# Schematic_1.net
KiCad netlist of a schematic drawn in Altium Designer
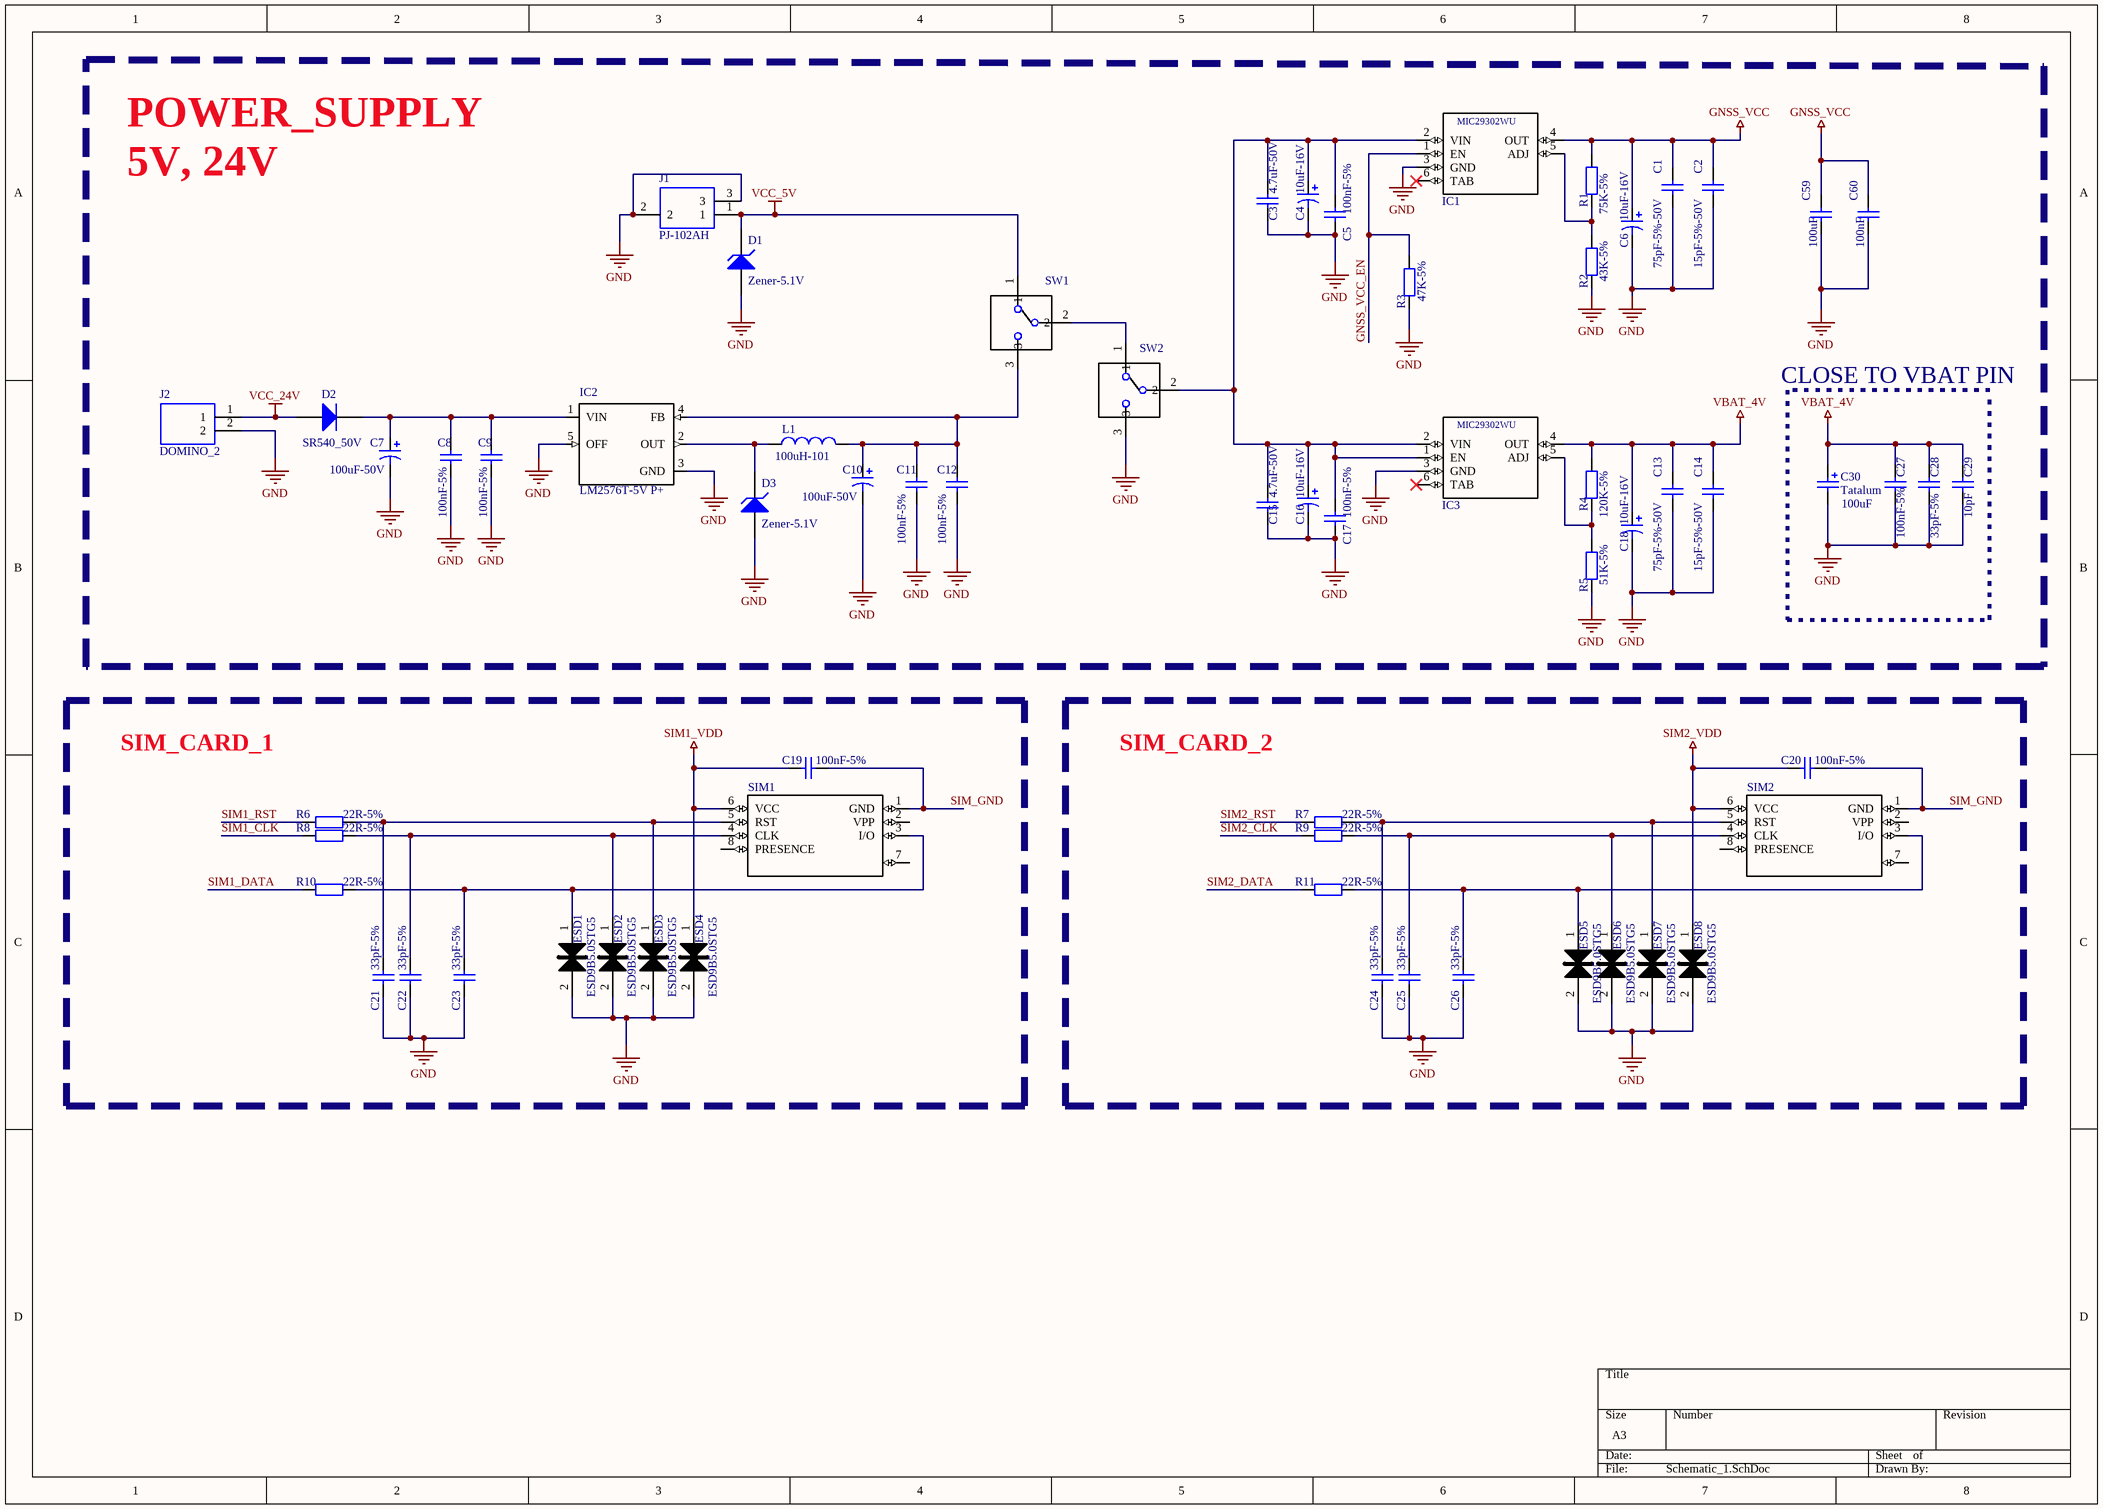
[diagram p0: Schematic_1.SchDoc]

(export (version "E")
  (design (tool "Eeschema 10.0.6"))
  (components
    (comp (ref "C1")
      (value "75pF-5%-50V")
      (footprint "6-0805_L")
      (description "Capacitor")
      (fields (field (name "Comment") "Cap") (field (name "PUBLISHER") "Altium Limited"))
      (libsource (lib "Miscellaneous Devices") (part "Cap"))
    )
    (comp (ref "C2")
      (value "15pF-5%-50V")
      (footprint "C0805")
      (description "Capacitor")
      (fields (field (name "Comment") "Cap") (field (name "PUBLISHER") "Altium Limited"))
      (libsource (lib "Miscellaneous Devices") (part "Cap"))
    )
    (comp (ref "C3")
      (value "4.7uF-50V")
      (footprint "C0805")
      (description "Capacitor")
      (fields (field (name "Comment") "Cap") (field (name "PUBLISHER") "Altium Limited"))
      (libsource (lib "Miscellaneous Devices") (part "Cap"))
    )
    (comp (ref "C4")
      (value "10uF-16V")
      (footprint "c0805")
      (description "Polarized Capacitor (Radial)")
      (fields (field (name "Comment") "Cap Pol1") (field (name "PUBLISHER") "Altium Limited"))
      (libsource (lib "Miscellaneous Devices") (part "Cap Pol1"))
    )
    (comp (ref "C5")
      (value "100nF-5%")
      (footprint "C0805")
      (description "Capacitor")
      (fields (field (name "Comment") "Cap") (field (name "PUBLISHER") "Altium Limited"))
      (libsource (lib "Miscellaneous Devices") (part "Cap"))
    )
    (comp (ref "C6")
      (value "10uF-16V")
      (footprint "C0805")
      (description "Polarized Capacitor (Radial)")
      (fields (field (name "Comment") "Cap Pol1") (field (name "PUBLISHER") "Altium Limited"))
      (libsource (lib "Miscellaneous Devices") (part "Cap Pol1"))
    )
    (comp (ref "C7")
      (value "100uF-50V")
      (footprint "CAP_ALUM_100uF_8x10")
      (description "Polarized Capacitor (Surface Mount)")
      (fields (field (name "Comment") "Cap Pol3") (field (name "PUBLISHER") "Altium Limited"))
      (libsource (lib "Miscellaneous Devices") (part "Cap Pol3"))
    )
    (comp (ref "C8")
      (value "100nF-5%")
      (footprint "6-0805_L")
      (description "Capacitor")
      (fields (field (name "Comment") "Cap") (field (name "PUBLISHER") "Altium Limited"))
      (libsource (lib "Miscellaneous Devices") (part "Cap"))
    )
    (comp (ref "C9")
      (value "100nF-5%")
      (footprint "6-0805_L")
      (description "Capacitor")
      (fields (field (name "Comment") "Cap") (field (name "PUBLISHER") "Altium Limited"))
      (libsource (lib "Miscellaneous Devices") (part "Cap"))
    )
    (comp (ref "C10")
      (value "100uF-50V")
      (footprint "CAP_ALUM_100uF_8x10")
      (description "Polarized Capacitor (Surface Mount)")
      (fields (field (name "Comment") "Cap Pol3") (field (name "PUBLISHER") "Altium Limited"))
      (libsource (lib "Miscellaneous Devices") (part "Cap Pol3"))
    )
    (comp (ref "C11")
      (value "100nF-5%")
      (footprint "6-0805_L")
      (description "Capacitor")
      (fields (field (name "Comment") "Cap") (field (name "PUBLISHER") "Altium Limited"))
      (libsource (lib "Miscellaneous Devices") (part "Cap"))
    )
    (comp (ref "C12")
      (value "100nF-5%")
      (footprint "6-0805_L")
      (description "Capacitor")
      (fields (field (name "Comment") "Cap") (field (name "PUBLISHER") "Altium Limited"))
      (libsource (lib "Miscellaneous Devices") (part "Cap"))
    )
    (comp (ref "C13")
      (value "75pF-5%-50V")
      (footprint "6-0805_L")
      (description "Capacitor")
      (fields (field (name "Comment") "Cap") (field (name "PUBLISHER") "Altium Limited"))
      (libsource (lib "Miscellaneous Devices") (part "Cap"))
    )
    (comp (ref "C14")
      (value "15pF-5%-50V")
      (footprint "C0805")
      (description "Capacitor")
      (fields (field (name "Comment") "Cap") (field (name "PUBLISHER") "Altium Limited"))
      (libsource (lib "Miscellaneous Devices") (part "Cap"))
    )
    (comp (ref "C15")
      (value "4.7uF-50V")
      (footprint "C0805")
      (description "Capacitor")
      (fields (field (name "Comment") "Cap") (field (name "PUBLISHER") "Altium Limited"))
      (libsource (lib "Miscellaneous Devices") (part "Cap"))
    )
    (comp (ref "C16")
      (value "10uF-16V")
      (footprint "c0805")
      (description "Polarized Capacitor (Radial)")
      (fields (field (name "Comment") "Cap Pol1") (field (name "PUBLISHER") "Altium Limited"))
      (libsource (lib "Miscellaneous Devices") (part "Cap Pol1"))
    )
    (comp (ref "C17")
      (value "100nF-5%")
      (footprint "C0805")
      (description "Capacitor")
      (fields (field (name "Comment") "Cap") (field (name "PUBLISHER") "Altium Limited"))
      (libsource (lib "Miscellaneous Devices") (part "Cap"))
    )
    (comp (ref "C18")
      (value "10uF-16V")
      (footprint "C0805")
      (description "Polarized Capacitor (Radial)")
      (fields (field (name "Comment") "Cap Pol1") (field (name "PUBLISHER") "Altium Limited"))
      (libsource (lib "Miscellaneous Devices") (part "Cap Pol1"))
    )
    (comp (ref "C19")
      (value "100nF-5%")
      (footprint "6-0805_L")
      (description "Capacitor")
      (fields (field (name "Comment") "Cap") (field (name "PUBLISHER") "Altium Limited"))
      (libsource (lib "Miscellaneous Devices") (part "Cap"))
    )
    (comp (ref "C20")
      (value "100nF-5%")
      (footprint "6-0805_L")
      (description "Capacitor")
      (fields (field (name "Comment") "Cap") (field (name "PUBLISHER") "Altium Limited"))
      (libsource (lib "Miscellaneous Devices") (part "Cap"))
    )
    (comp (ref "C21")
      (value "33pF-5%")
      (footprint "6-0805_L")
      (description "Capacitor")
      (fields (field (name "Comment") "Cap") (field (name "PUBLISHER") "Altium Limited"))
      (libsource (lib "Miscellaneous Devices") (part "Cap"))
    )
    (comp (ref "C22")
      (value "33pF-5%")
      (footprint "6-0805_L")
      (description "Capacitor")
      (fields (field (name "Comment") "Cap") (field (name "PUBLISHER") "Altium Limited"))
      (libsource (lib "Miscellaneous Devices") (part "Cap"))
    )
    (comp (ref "C23")
      (value "33pF-5%")
      (footprint "6-0805_L")
      (description "Capacitor")
      (fields (field (name "Comment") "Cap") (field (name "PUBLISHER") "Altium Limited"))
      (libsource (lib "Miscellaneous Devices") (part "Cap"))
    )
    (comp (ref "C24")
      (value "33pF-5%")
      (footprint "6-0805_L")
      (description "Capacitor")
      (fields (field (name "Comment") "Cap") (field (name "PUBLISHER") "Altium Limited"))
      (libsource (lib "Miscellaneous Devices") (part "Cap"))
    )
    (comp (ref "C25")
      (value "33pF-5%")
      (footprint "6-0805_L")
      (description "Capacitor")
      (fields (field (name "Comment") "Cap") (field (name "PUBLISHER") "Altium Limited"))
      (libsource (lib "Miscellaneous Devices") (part "Cap"))
    )
    (comp (ref "C26")
      (value "33pF-5%")
      (footprint "6-0805_L")
      (description "Capacitor")
      (fields (field (name "Comment") "Cap") (field (name "PUBLISHER") "Altium Limited"))
      (libsource (lib "Miscellaneous Devices") (part "Cap"))
    )
    (comp (ref "C27")
      (value "100nF-5%")
      (footprint "C0805")
      (description "Capacitor")
      (fields (field (name "Comment") "Cap") (field (name "PUBLISHER") "Altium Limited"))
      (libsource (lib "Miscellaneous Devices") (part "Cap"))
    )
    (comp (ref "C28")
      (value "33pF-5%")
      (footprint "C0805")
      (description "Capacitor")
      (fields (field (name "Comment") "Cap") (field (name "PUBLISHER") "Altium Limited"))
      (libsource (lib "Miscellaneous Devices") (part "Cap"))
    )
    (comp (ref "C29")
      (value "10pF")
      (footprint "C0805")
      (description "Capacitor")
      (fields (field (name "Comment") "Cap") (field (name "PUBLISHER") "Altium Limited"))
      (libsource (lib "Miscellaneous Devices") (part "Cap"))
    )
    (comp (ref "C30")
      (value "Tatalum")
      (footprint "Tantalum_7343")
      (description "Polarized Capacitor (Axial)")
      (fields (field (name "ALTIUM_VALUE") "100uF") (field (name "PUBLISHER") "Altium Limited"))
      (libsource (lib "Miscellaneous Devices") (part "Cap Pol2"))
    )
    (comp (ref "C59")
      (value "100uF")
      (footprint "6-0805_L")
      (description "Capacitor")
      (fields (field (name "Comment") "Cap") (field (name "PUBLISHER") "Altium Limited"))
      (libsource (lib "Miscellaneous Devices") (part "Cap"))
    )
    (comp (ref "C60")
      (value "100nF")
      (footprint "6-0805_L")
      (description "Capacitor")
      (fields (field (name "Comment") "Cap") (field (name "PUBLISHER") "Altium Limited"))
      (libsource (lib "Miscellaneous Devices") (part "Cap"))
    )
    (comp (ref "D1")
      (value "Zener-5.1V")
      (footprint "Zener_SMD")
      (description "Zener Diode")
      (fields (field (name "PUBLISHER") "Altium Limited"))
      (libsource (lib "Miscellaneous Devices") (part "D Zener"))
    )
    (comp (ref "D2")
      (value "SR540_50V")
      (footprint "DIODE_40V_5A")
      (description "Default Diode")
      (fields (field (name "PUBLISHER") "Altium Limited"))
      (libsource (lib "Miscellaneous Devices") (part "Diode"))
    )
    (comp (ref "D3")
      (value "Zener-5.1V")
      (footprint "Zener_SMD")
      (description "Zener Diode")
      (fields (field (name "PUBLISHER") "Altium Limited"))
      (libsource (lib "Miscellaneous Devices") (part "D Zener"))
    )
    (comp (ref "ESD1")
      (value "ESD9B5.0STG5")
      (footprint "ESD9B5.0STG5")
      (libsource (lib "ESD9B5") (part "1"))
    )
    (comp (ref "ESD2")
      (value "ESD9B5.0STG5")
      (footprint "ESD9B5.0STG5")
      (libsource (lib "ESD9B5") (part "1"))
    )
    (comp (ref "ESD3")
      (value "ESD9B5.0STG5")
      (footprint "ESD9B5.0STG5")
      (libsource (lib "ESD9B5") (part "1"))
    )
    (comp (ref "ESD4")
      (value "ESD9B5.0STG5")
      (footprint "ESD9B5.0STG5")
      (libsource (lib "ESD9B5") (part "1"))
    )
    (comp (ref "ESD5")
      (value "ESD9B5.0STG5")
      (footprint "ESD9B5.0STG5")
      (libsource (lib "ESD9B5") (part "1"))
    )
    (comp (ref "ESD6")
      (value "ESD9B5.0STG5")
      (footprint "ESD9B5.0STG5")
      (libsource (lib "ESD9B5") (part "1"))
    )
    (comp (ref "ESD7")
      (value "ESD9B5.0STG5")
      (footprint "ESD9B5.0STG5")
      (libsource (lib "ESD9B5") (part "1"))
    )
    (comp (ref "ESD8")
      (value "ESD9B5.0STG5")
      (footprint "ESD9B5.0STG5")
      (libsource (lib "ESD9B5") (part "1"))
    )
    (comp (ref "IC1")
      (value "MIC29302WU")
      (footprint "MIC29302WU_3D")
      (description "MIC29302 Series 3 A 1.24 to 26 V ADJ Output Voltage LDO Regulator - TO-263-5")
      (fields (field (name "MF") "Microchip"))
      (libsource (lib "MIC29302WU") (part "MIC29302WU"))
    )
    (comp (ref "IC2")
      (value "LM2576T-5V P+")
      (footprint "MIC29302WU_3D")
      (description "Integrated Circuit")
      (fields (field (name "MF") "National Semiconductor") (field (name "MP") "LM2576"))
      (libsource (lib "LM2576") (part "LM2576"))
    )
    (comp (ref "IC3")
      (value "MIC29302WU")
      (footprint "MIC29302WU_3D")
      (description "MIC29302 Series 3 A 1.24 to 26 V ADJ Output Voltage LDO Regulator - TO-263-5")
      (fields (field (name "MF") "Microchip"))
      (libsource (lib "MIC29302WU") (part "MIC29302WU"))
    )
    (comp (ref "J1")
      (value "PJ-102AH")
      (footprint "DC_Jack")
      (description "DC POWER JACK")
      (libsource (lib "PJ-102AH") (part "PJ-102AH"))
    )
    (comp (ref "J2")
      (value "DOMINO_2")
      (footprint "DOMINO_2")
      (description "2 way std vertical terminal,5.08mm pitch")
      (fields (field (name "MANUFACTURER_PART_NUMBER") "1715721") (field (name "RS PART NUMBER") "1930564"))
      (libsource (lib "1715721") (part "1715721"))
    )
    (comp (ref "L1")
      (value "100uH-101")
      (footprint "INDUCTOR_SMD_12x12")
      (description "Inductor")
      (fields (field (name "PUBLISHER") "Altium Limited"))
      (libsource (lib "Miscellaneous Devices") (part "Inductor"))
    )
    (comp (ref "R1")
      (value "75K-5%")
      (footprint "6-0805_L")
      (description "Resistor")
      (fields (field (name "Comment") "Res2") (field (name "PUBLISHER") "Altium Limited"))
      (libsource (lib "") (part "Res2_1"))
    )
    (comp (ref "R2")
      (value "43K-5%")
      (footprint "6-0805_L")
      (description "Resistor")
      (fields (field (name "Comment") "Res2") (field (name "PUBLISHER") "Altium Limited"))
      (libsource (lib "") (part "Res2_1"))
    )
    (comp (ref "R3")
      (value "47K-5%")
      (footprint "6-0805_L")
      (description "Resistor")
      (fields (field (name "PUBLISHER") "Altium Limited"))
      (libsource (lib "") (part "Res2_1"))
    )
    (comp (ref "R4")
      (value "120K-5%")
      (footprint "6-0805_L")
      (description "Resistor")
      (fields (field (name "Comment") "Res2") (field (name "PUBLISHER") "Altium Limited"))
      (libsource (lib "") (part "Res2_1"))
    )
    (comp (ref "R5")
      (value "51K-5%")
      (footprint "6-0805_L")
      (description "Resistor")
      (fields (field (name "Comment") "Res2") (field (name "PUBLISHER") "Altium Limited"))
      (libsource (lib "") (part "Res2_1"))
    )
    (comp (ref "R6")
      (value "22R-5%")
      (footprint "6-0805_L")
      (description "Resistor")
      (fields (field (name "Comment") "Res2") (field (name "PUBLISHER") "Altium Limited"))
      (libsource (lib "Miscellaneous Devices") (part "Res2"))
    )
    (comp (ref "R7")
      (value "22R-5%")
      (footprint "6-0805_L")
      (description "Resistor")
      (fields (field (name "Comment") "Res2") (field (name "PUBLISHER") "Altium Limited"))
      (libsource (lib "Miscellaneous Devices") (part "Res2"))
    )
    (comp (ref "R8")
      (value "22R-5%")
      (footprint "6-0805_L")
      (description "Resistor")
      (fields (field (name "Comment") "Res2") (field (name "PUBLISHER") "Altium Limited"))
      (libsource (lib "Miscellaneous Devices") (part "Res2"))
    )
    (comp (ref "R9")
      (value "22R-5%")
      (footprint "6-0805_L")
      (description "Resistor")
      (fields (field (name "Comment") "Res2") (field (name "PUBLISHER") "Altium Limited"))
      (libsource (lib "Miscellaneous Devices") (part "Res2"))
    )
    (comp (ref "R10")
      (value "22R-5%")
      (footprint "6-0805_L")
      (description "Resistor")
      (fields (field (name "Comment") "Res2") (field (name "PUBLISHER") "Altium Limited"))
      (libsource (lib "Miscellaneous Devices") (part "Res2"))
    )
    (comp (ref "R11")
      (value "22R-5%")
      (footprint "6-0805_L")
      (description "Resistor")
      (fields (field (name "Comment") "Res2") (field (name "PUBLISHER") "Altium Limited"))
      (libsource (lib "Miscellaneous Devices") (part "Res2"))
    )
    (comp (ref "SIM1")
      (value "912283001")
      (footprint "SIM_CARD")
      (description "2.54mm Pitch ChipSIM Connector with Ejector, 6 Circuits, without Pegs, Yellow Button")
      (fields (field (name "MP") "91228-3001") (field (name "MF") "Molex"))
      (libsource (lib "912283001") (part "912283001"))
    )
    (comp (ref "SIM2")
      (value "912283001")
      (footprint "SIM_CARD")
      (description "2.54mm Pitch ChipSIM Connector with Ejector, 6 Circuits, without Pegs, Yellow Button")
      (fields (field (name "MP") "91228-3001") (field (name "MF") "Molex"))
      (libsource (lib "912283001") (part "912283001"))
    )
    (comp (ref "SW1")
      (value "DIP-SLIDE-SWITCH(3P-11.6X4.0X5.4+2.0MM)")
      (footprint "SLIDE_SWITCH_3PINS")
      (description "EG Series SPDT On-On Vertical Through Hole Slide Switch")
      (fields (field (name "MF") "E-Switch") (field (name "MP") "EG1218"))
      (libsource (lib "DIP-SLIDE-SWITCH_3P-11.6X4.0X5.4_2.0MM_") (part "DIP-SLIDE-SWITCH(3P-11.6X4.0X5.4+2.0MM)"))
    )
    (comp (ref "SW2")
      (value "DIP-SLIDE-SWITCH(3P-11.6X4.0X5.4+2.0MM)")
      (footprint "SLIDE_SWITCH_3PINS")
      (description "EG Series SPDT On-On Vertical Through Hole Slide Switch")
      (fields (field (name "MF") "E-Switch") (field (name "MP") "EG1218"))
      (libsource (lib "DIP-SLIDE-SWITCH_3P-11.6X4.0X5.4_2.0MM_") (part "DIP-SLIDE-SWITCH(3P-11.6X4.0X5.4+2.0MM)"))
    )
  )
  (nets
    (net (code "1") (name "/GNSS_VCC_EN") (class "Default")
      (node (ref "IC1") (pin "1") (pinfunction "EN_1") (pintype "bidirectional"))
      (node (ref "R3") (pin "2") (pinfunction "2_2") (pintype "passive"))
    )
    (net (code "2") (name "/SIM1_CLK") (class "Default")
      (node (ref "R8") (pin "2") (pinfunction "2_2") (pintype "passive"))
    )
    (net (code "3") (name "/SIM1_DATA") (class "Default")
      (node (ref "R10") (pin "2") (pinfunction "2_2") (pintype "passive"))
    )
    (net (code "4") (name "/SIM1_RST") (class "Default")
      (node (ref "R6") (pin "2") (pinfunction "2_2") (pintype "passive"))
    )
    (net (code "5") (name "/SIM2_CLK") (class "Default")
      (node (ref "R9") (pin "2") (pinfunction "2_2") (pintype "passive"))
    )
    (net (code "6") (name "/SIM2_DATA") (class "Default")
      (node (ref "R11") (pin "2") (pinfunction "2_2") (pintype "passive"))
    )
    (net (code "7") (name "/SIM2_RST") (class "Default")
      (node (ref "R7") (pin "2") (pinfunction "2_2") (pintype "passive"))
    )
    (net (code "8") (name "/SIM_GND") (class "Default")
      (node (ref "C19") (pin "2") (pinfunction "2_2") (pintype "passive"))
      (node (ref "C20") (pin "2") (pinfunction "2_2") (pintype "passive"))
      (node (ref "SIM1") (pin "1") (pinfunction "GND_1") (pintype "bidirectional"))
      (node (ref "SIM2") (pin "1") (pinfunction "GND_1") (pintype "bidirectional"))
    )
    (net (code "9") (name "GND") (class "Default")
      (node (ref "C1") (pin "1") (pinfunction "1_1") (pintype "passive"))
      (node (ref "C10") (pin "2") (pinfunction "2_2") (pintype "passive"))
      (node (ref "C11") (pin "1") (pinfunction "1_1") (pintype "passive"))
      (node (ref "C12") (pin "1") (pinfunction "1_1") (pintype "passive"))
      (node (ref "C13") (pin "1") (pinfunction "1_1") (pintype "passive"))
      (node (ref "C14") (pin "1") (pinfunction "1_1") (pintype "passive"))
      (node (ref "C15") (pin "1") (pinfunction "1_1") (pintype "passive"))
      (node (ref "C16") (pin "2") (pinfunction "2_2") (pintype "passive"))
      (node (ref "C17") (pin "1") (pinfunction "1_1") (pintype "passive"))
      (node (ref "C18") (pin "2") (pinfunction "2_2") (pintype "passive"))
      (node (ref "C2") (pin "1") (pinfunction "1_1") (pintype "passive"))
      (node (ref "C21") (pin "1") (pinfunction "1_1") (pintype "passive"))
      (node (ref "C22") (pin "1") (pinfunction "1_1") (pintype "passive"))
      (node (ref "C23") (pin "1") (pinfunction "1_1") (pintype "passive"))
      (node (ref "C24") (pin "1") (pinfunction "1_1") (pintype "passive"))
      (node (ref "C25") (pin "1") (pinfunction "1_1") (pintype "passive"))
      (node (ref "C26") (pin "1") (pinfunction "1_1") (pintype "passive"))
      (node (ref "C27") (pin "1") (pinfunction "1_1") (pintype "passive"))
      (node (ref "C28") (pin "2") (pinfunction "2_2") (pintype "passive"))
      (node (ref "C29") (pin "1") (pinfunction "1_1") (pintype "passive"))
      (node (ref "C3") (pin "1") (pinfunction "1_1") (pintype "passive"))
      (node (ref "C30") (pin "2") (pinfunction "2_2") (pintype "passive"))
      (node (ref "C4") (pin "2") (pinfunction "2_2") (pintype "passive"))
      (node (ref "C5") (pin "1") (pinfunction "1_1") (pintype "passive"))
      (node (ref "C59") (pin "1") (pinfunction "1_1") (pintype "passive"))
      (node (ref "C6") (pin "2") (pinfunction "2_2") (pintype "passive"))
      (node (ref "C60") (pin "1") (pinfunction "1_1") (pintype "passive"))
      (node (ref "C7") (pin "2") (pinfunction "2_2") (pintype "passive"))
      (node (ref "C8") (pin "1") (pinfunction "1_1") (pintype "passive"))
      (node (ref "C9") (pin "1") (pinfunction "1_1") (pintype "passive"))
      (node (ref "D1") (pin "1") (pinfunction "A_1") (pintype "passive"))
      (node (ref "D3") (pin "1") (pinfunction "A_1") (pintype "passive"))
      (node (ref "ESD1") (pin "2") (pinfunction "K_2") (pintype "passive"))
      (node (ref "ESD2") (pin "2") (pinfunction "K_2") (pintype "passive"))
      (node (ref "ESD3") (pin "2") (pinfunction "K_2") (pintype "passive"))
      (node (ref "ESD4") (pin "2") (pinfunction "K_2") (pintype "passive"))
      (node (ref "ESD5") (pin "2") (pinfunction "K_2") (pintype "passive"))
      (node (ref "ESD6") (pin "2") (pinfunction "K_2") (pintype "passive"))
      (node (ref "ESD7") (pin "2") (pinfunction "K_2") (pintype "passive"))
      (node (ref "ESD8") (pin "2") (pinfunction "K_2") (pintype "passive"))
      (node (ref "IC1") (pin "3") (pinfunction "GND_3") (pintype "bidirectional"))
      (node (ref "IC2") (pin "3") (pinfunction "GND_3") (pintype "power_in"))
      (node (ref "IC2") (pin "5") (pinfunction "OFF_5") (pintype "input"))
      (node (ref "IC3") (pin "3") (pinfunction "GND_3") (pintype "bidirectional"))
      (node (ref "J1") (pin "2") (pinfunction "2_2") (pintype "passive"))
      (node (ref "J1") (pin "3") (pinfunction "3_3") (pintype "passive"))
      (node (ref "J2") (pin "2") (pinfunction "2_2") (pintype "passive"))
      (node (ref "R2") (pin "1") (pinfunction "1_1") (pintype "passive"))
      (node (ref "R3") (pin "1") (pinfunction "1_1") (pintype "passive"))
      (node (ref "R5") (pin "1") (pinfunction "1_1") (pintype "passive"))
      (node (ref "SW2") (pin "3") (pinfunction "3_3") (pintype "bidirectional"))
    )
    (net (code "10") (name "GNSS_VCC") (class "Default")
      (node (ref "C1") (pin "2") (pinfunction "2_2") (pintype "passive"))
      (node (ref "C2") (pin "2") (pinfunction "2_2") (pintype "passive"))
      (node (ref "C59") (pin "2") (pinfunction "2_2") (pintype "passive"))
      (node (ref "C6") (pin "1") (pinfunction "1_1") (pintype "passive"))
      (node (ref "C60") (pin "2") (pinfunction "2_2") (pintype "passive"))
      (node (ref "IC1") (pin "4") (pinfunction "OUT_4") (pintype "bidirectional"))
      (node (ref "R1") (pin "2") (pinfunction "2_2") (pintype "passive"))
    )
    (net (code "11") (name "Net-(D2-K)") (class "Default")
      (node (ref "C7") (pin "1") (pinfunction "1_1") (pintype "passive"))
      (node (ref "C8") (pin "2") (pinfunction "2_2") (pintype "passive"))
      (node (ref "C9") (pin "2") (pinfunction "2_2") (pintype "passive"))
      (node (ref "D2") (pin "2") (pinfunction "K_2") (pintype "passive"))
      (node (ref "IC2") (pin "1") (pinfunction "VIN_1") (pintype "power_in"))
    )
    (net (code "12") (name "Net-(D3-K)") (class "Default")
      (node (ref "D3") (pin "2") (pinfunction "K_2") (pintype "passive"))
      (node (ref "IC2") (pin "2") (pinfunction "OUT_2") (pintype "output"))
      (node (ref "L1") (pin "1") (pinfunction "1_1") (pintype "passive"))
    )
    (net (code "13") (name "Net-(ESD1-A)") (class "Default")
      (node (ref "C23") (pin "2") (pinfunction "2_2") (pintype "passive"))
      (node (ref "ESD1") (pin "1") (pinfunction "A_1") (pintype "passive"))
      (node (ref "R10") (pin "1") (pinfunction "1_1") (pintype "passive"))
      (node (ref "SIM1") (pin "3") (pinfunction "I/O_3") (pintype "bidirectional"))
    )
    (net (code "14") (name "Net-(ESD2-A)") (class "Default")
      (node (ref "C22") (pin "2") (pinfunction "2_2") (pintype "passive"))
      (node (ref "ESD2") (pin "1") (pinfunction "A_1") (pintype "passive"))
      (node (ref "R8") (pin "1") (pinfunction "1_1") (pintype "passive"))
      (node (ref "SIM1") (pin "4") (pinfunction "CLK_4") (pintype "bidirectional"))
    )
    (net (code "15") (name "Net-(ESD3-A)") (class "Default")
      (node (ref "C21") (pin "2") (pinfunction "2_2") (pintype "passive"))
      (node (ref "ESD3") (pin "1") (pinfunction "A_1") (pintype "passive"))
      (node (ref "R6") (pin "1") (pinfunction "1_1") (pintype "passive"))
      (node (ref "SIM1") (pin "5") (pinfunction "RST_5") (pintype "bidirectional"))
    )
    (net (code "16") (name "Net-(ESD5-A)") (class "Default")
      (node (ref "C26") (pin "2") (pinfunction "2_2") (pintype "passive"))
      (node (ref "ESD5") (pin "1") (pinfunction "A_1") (pintype "passive"))
      (node (ref "R11") (pin "1") (pinfunction "1_1") (pintype "passive"))
      (node (ref "SIM2") (pin "3") (pinfunction "I/O_3") (pintype "bidirectional"))
    )
    (net (code "17") (name "Net-(ESD6-A)") (class "Default")
      (node (ref "C25") (pin "2") (pinfunction "2_2") (pintype "passive"))
      (node (ref "ESD6") (pin "1") (pinfunction "A_1") (pintype "passive"))
      (node (ref "R9") (pin "1") (pinfunction "1_1") (pintype "passive"))
      (node (ref "SIM2") (pin "4") (pinfunction "CLK_4") (pintype "bidirectional"))
    )
    (net (code "18") (name "Net-(ESD7-A)") (class "Default")
      (node (ref "C24") (pin "2") (pinfunction "2_2") (pintype "passive"))
      (node (ref "ESD7") (pin "1") (pinfunction "A_1") (pintype "passive"))
      (node (ref "R7") (pin "1") (pinfunction "1_1") (pintype "passive"))
      (node (ref "SIM2") (pin "5") (pinfunction "RST_5") (pintype "bidirectional"))
    )
    (net (code "19") (name "Net-(IC1-ADJ)") (class "Default")
      (node (ref "IC1") (pin "5") (pinfunction "ADJ_5") (pintype "bidirectional"))
      (node (ref "R1") (pin "1") (pinfunction "1_1") (pintype "passive"))
      (node (ref "R2") (pin "2") (pinfunction "2_2") (pintype "passive"))
    )
    (net (code "20") (name "Net-(IC1-VIN)") (class "Default")
      (node (ref "C15") (pin "2") (pinfunction "2_2") (pintype "passive"))
      (node (ref "C16") (pin "1") (pinfunction "1_1") (pintype "passive"))
      (node (ref "C17") (pin "2") (pinfunction "2_2") (pintype "passive"))
      (node (ref "C3") (pin "2") (pinfunction "2_2") (pintype "passive"))
      (node (ref "C4") (pin "1") (pinfunction "1_1") (pintype "passive"))
      (node (ref "C5") (pin "2") (pinfunction "2_2") (pintype "passive"))
      (node (ref "IC1") (pin "2") (pinfunction "VIN_2") (pintype "bidirectional"))
      (node (ref "IC3") (pin "1") (pinfunction "EN_1") (pintype "bidirectional"))
      (node (ref "IC3") (pin "2") (pinfunction "VIN_2") (pintype "bidirectional"))
      (node (ref "SW2") (pin "2") (pinfunction "2_2") (pintype "bidirectional"))
    )
    (net (code "21") (name "Net-(IC2-FB)") (class "Default")
      (node (ref "C10") (pin "1") (pinfunction "1_1") (pintype "passive"))
      (node (ref "C11") (pin "2") (pinfunction "2_2") (pintype "passive"))
      (node (ref "C12") (pin "2") (pinfunction "2_2") (pintype "passive"))
      (node (ref "IC2") (pin "4") (pinfunction "FB_4") (pintype "input"))
      (node (ref "L1") (pin "2") (pinfunction "2_2") (pintype "passive"))
      (node (ref "SW1") (pin "3") (pinfunction "3_3") (pintype "bidirectional"))
    )
    (net (code "22") (name "Net-(IC3-ADJ)") (class "Default")
      (node (ref "IC3") (pin "5") (pinfunction "ADJ_5") (pintype "bidirectional"))
      (node (ref "R4") (pin "1") (pinfunction "1_1") (pintype "passive"))
      (node (ref "R5") (pin "2") (pinfunction "2_2") (pintype "passive"))
    )
    (net (code "23") (name "Net-(SW1-Pad2)") (class "Default")
      (node (ref "SW1") (pin "2") (pinfunction "2_2") (pintype "bidirectional"))
      (node (ref "SW2") (pin "1") (pinfunction "1_1") (pintype "bidirectional"))
    )
    (net (code "24") (name "SIM1_VDD") (class "Default")
      (node (ref "C19") (pin "1") (pinfunction "1_1") (pintype "passive"))
      (node (ref "ESD4") (pin "1") (pinfunction "A_1") (pintype "passive"))
      (node (ref "SIM1") (pin "6") (pinfunction "VCC_6") (pintype "bidirectional"))
    )
    (net (code "25") (name "SIM2_VDD") (class "Default")
      (node (ref "C20") (pin "1") (pinfunction "1_1") (pintype "passive"))
      (node (ref "ESD8") (pin "1") (pinfunction "A_1") (pintype "passive"))
      (node (ref "SIM2") (pin "6") (pinfunction "VCC_6") (pintype "bidirectional"))
    )
    (net (code "26") (name "VBAT_4V") (class "Default")
      (node (ref "C13") (pin "2") (pinfunction "2_2") (pintype "passive"))
      (node (ref "C14") (pin "2") (pinfunction "2_2") (pintype "passive"))
      (node (ref "C18") (pin "1") (pinfunction "1_1") (pintype "passive"))
      (node (ref "C27") (pin "2") (pinfunction "2_2") (pintype "passive"))
      (node (ref "C28") (pin "1") (pinfunction "1_1") (pintype "passive"))
      (node (ref "C29") (pin "2") (pinfunction "2_2") (pintype "passive"))
      (node (ref "C30") (pin "1") (pinfunction "1_1") (pintype "passive"))
      (node (ref "IC3") (pin "4") (pinfunction "OUT_4") (pintype "bidirectional"))
      (node (ref "R4") (pin "2") (pinfunction "2_2") (pintype "passive"))
    )
    (net (code "27") (name "VCC_5V") (class "Default")
      (node (ref "D1") (pin "2") (pinfunction "K_2") (pintype "passive"))
      (node (ref "J1") (pin "1") (pinfunction "1_1") (pintype "passive"))
      (node (ref "SW1") (pin "1") (pinfunction "1_1") (pintype "bidirectional"))
    )
    (net (code "28") (name "VCC_24V") (class "Default")
      (node (ref "D2") (pin "1") (pinfunction "A_1") (pintype "passive"))
      (node (ref "J2") (pin "1") (pinfunction "1_1") (pintype "passive"))
    )
    (net (code "29") (name "unconnected-(IC1-TAB-Pad6)") (class "Default")
      (node (ref "IC1") (pin "6") (pinfunction "TAB_6") (pintype "bidirectional+no_connect"))
    )
    (net (code "30") (name "unconnected-(IC3-TAB-Pad6)") (class "Default")
      (node (ref "IC3") (pin "6") (pinfunction "TAB_6") (pintype "bidirectional+no_connect"))
    )
    (net (code "31") (name "unconnected-(SIM1-PRESENCE-Pad8)") (class "Default")
      (node (ref "SIM1") (pin "8") (pinfunction "PRESENCE_8") (pintype "bidirectional"))
    )
    (net (code "32") (name "unconnected-(SIM1-Pad7)") (class "Default")
      (node (ref "SIM1") (pin "7") (pintype "bidirectional"))
    )
    (net (code "33") (name "unconnected-(SIM1-VPP-Pad2)") (class "Default")
      (node (ref "SIM1") (pin "2") (pinfunction "VPP_2") (pintype "bidirectional"))
    )
    (net (code "34") (name "unconnected-(SIM2-PRESENCE-Pad8)") (class "Default")
      (node (ref "SIM2") (pin "8") (pinfunction "PRESENCE_8") (pintype "bidirectional"))
    )
    (net (code "35") (name "unconnected-(SIM2-Pad7)") (class "Default")
      (node (ref "SIM2") (pin "7") (pintype "bidirectional"))
    )
    (net (code "36") (name "unconnected-(SIM2-VPP-Pad2)") (class "Default")
      (node (ref "SIM2") (pin "2") (pinfunction "VPP_2") (pintype "bidirectional"))
    )
  )
)
